# CheetahBooster.net
KiCad netlist of a schematic drawn in EAGLE
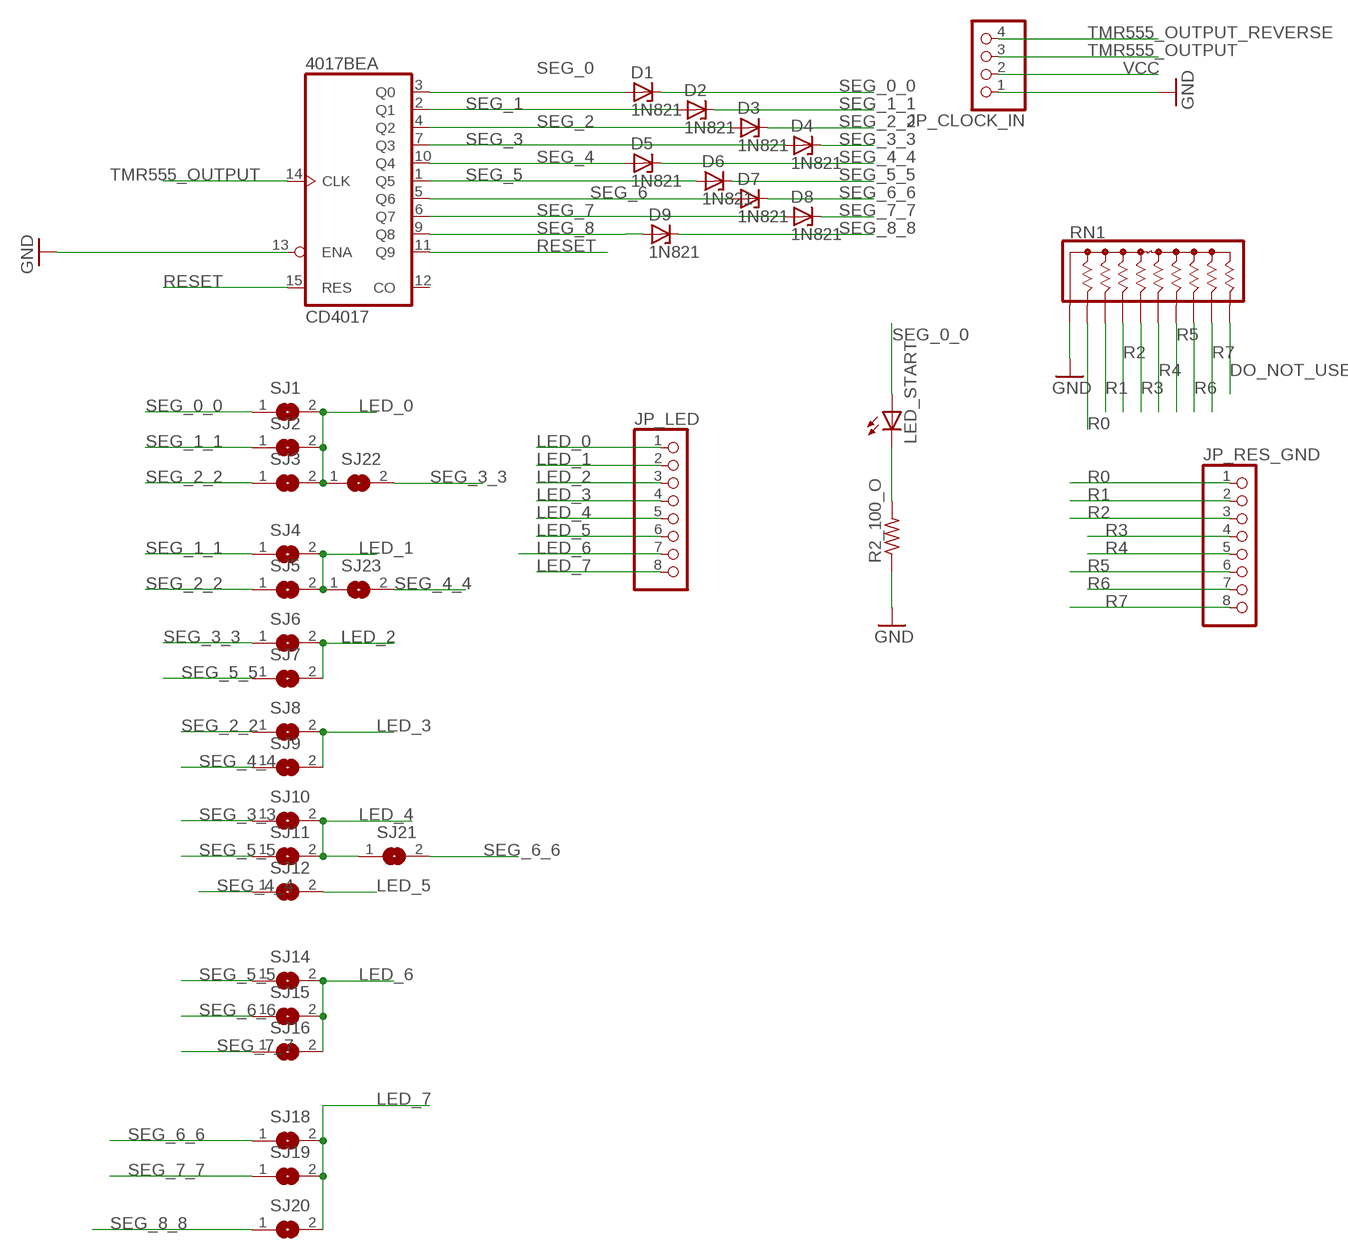
[diagram p0: schematic, sheet 1]

(export (version "E")
  (design (tool "Eeschema 10.0.6"))
  (components
    (comp (ref "4017BE")
      (value "CD4017")
      (footprint "eagle-import:DIL16")
      (libsource (lib "eagle-import") (part "CD4017"))
    )
    (comp (ref "D1")
      (value "1N821")
      (footprint "eagle-import:DO35Z10")
      (libsource (lib "eagle-import") (part "1N821"))
    )
    (comp (ref "D2")
      (value "1N821")
      (footprint "eagle-import:DO35Z10")
      (libsource (lib "eagle-import") (part "1N821"))
    )
    (comp (ref "D3")
      (value "1N821")
      (footprint "eagle-import:DO35Z10")
      (libsource (lib "eagle-import") (part "1N821"))
    )
    (comp (ref "D4")
      (value "1N821")
      (footprint "eagle-import:DO35Z10")
      (libsource (lib "eagle-import") (part "1N821"))
    )
    (comp (ref "D5")
      (value "1N821")
      (footprint "eagle-import:DO35Z10")
      (libsource (lib "eagle-import") (part "1N821"))
    )
    (comp (ref "D6")
      (value "1N821")
      (footprint "eagle-import:DO35Z10")
      (libsource (lib "eagle-import") (part "1N821"))
    )
    (comp (ref "D7")
      (value "1N821")
      (footprint "eagle-import:DO35Z10")
      (libsource (lib "eagle-import") (part "1N821"))
    )
    (comp (ref "D8")
      (value "1N821")
      (footprint "eagle-import:DO35Z10")
      (libsource (lib "eagle-import") (part "1N821"))
    )
    (comp (ref "D9")
      (value "1N821")
      (footprint "eagle-import:DO35Z10")
      (libsource (lib "eagle-import") (part "1N821"))
    )
    (comp (ref "JP_CLOCK_IN")
      (value "PINHD-1X4")
      (footprint "eagle-import:1X04")
      (libsource (lib "eagle-import") (part "PINHD-1X4"))
    )
    (comp (ref "JP_LED")
      (value "PINHD-1X8")
      (footprint "eagle-import:1X08")
      (libsource (lib "eagle-import") (part "PINHD-1X8"))
    )
    (comp (ref "JP_RES_GND")
      (value "PINHD-1X8")
      (footprint "eagle-import:1X08")
      (libsource (lib "eagle-import") (part "PINHD-1X8"))
    )
    (comp (ref "LED_START")
      (value "LEDSMT1206")
      (footprint "eagle-import:1206")
      (libsource (lib "eagle-import") (part "LEDSMT1206"))
    )
    (comp (ref "R2_100_O")
      (value "R-US_R1206")
      (footprint "eagle-import:R1206")
      (libsource (lib "eagle-import") (part "R-US_R1206"))
    )
    (comp (ref "RN1")
      (value "4610X")
      (footprint "eagle-import:SIP10")
      (libsource (lib "eagle-import") (part "4610X"))
    )
    (comp (ref "SJ1")
      (value "SOLDERJUMPER")
      (footprint "eagle-import:SOLDERJUMPER_ARROW_NOPASTE")
      (libsource (lib "eagle-import") (part "SOLDERJUMPER"))
    )
    (comp (ref "SJ2")
      (value "SOLDERJUMPER")
      (footprint "eagle-import:SOLDERJUMPER_ARROW_NOPASTE")
      (libsource (lib "eagle-import") (part "SOLDERJUMPER"))
    )
    (comp (ref "SJ3")
      (value "SOLDERJUMPER")
      (footprint "eagle-import:SOLDERJUMPER_ARROW_NOPASTE")
      (libsource (lib "eagle-import") (part "SOLDERJUMPER"))
    )
    (comp (ref "SJ4")
      (value "SOLDERJUMPER")
      (footprint "eagle-import:SOLDERJUMPER_ARROW_NOPASTE")
      (libsource (lib "eagle-import") (part "SOLDERJUMPER"))
    )
    (comp (ref "SJ5")
      (value "SOLDERJUMPER")
      (footprint "eagle-import:SOLDERJUMPER_ARROW_NOPASTE")
      (libsource (lib "eagle-import") (part "SOLDERJUMPER"))
    )
    (comp (ref "SJ6")
      (value "SOLDERJUMPER")
      (footprint "eagle-import:SOLDERJUMPER_ARROW_NOPASTE")
      (libsource (lib "eagle-import") (part "SOLDERJUMPER"))
    )
    (comp (ref "SJ7")
      (value "SOLDERJUMPER")
      (footprint "eagle-import:SOLDERJUMPER_ARROW_NOPASTE")
      (libsource (lib "eagle-import") (part "SOLDERJUMPER"))
    )
    (comp (ref "SJ8")
      (value "SOLDERJUMPER")
      (footprint "eagle-import:SOLDERJUMPER_ARROW_NOPASTE")
      (libsource (lib "eagle-import") (part "SOLDERJUMPER"))
    )
    (comp (ref "SJ9")
      (value "SOLDERJUMPER")
      (footprint "eagle-import:SOLDERJUMPER_ARROW_NOPASTE")
      (libsource (lib "eagle-import") (part "SOLDERJUMPER"))
    )
    (comp (ref "SJ10")
      (value "SOLDERJUMPER")
      (footprint "eagle-import:SOLDERJUMPER_ARROW_NOPASTE")
      (libsource (lib "eagle-import") (part "SOLDERJUMPER"))
    )
    (comp (ref "SJ11")
      (value "SOLDERJUMPER")
      (footprint "eagle-import:SOLDERJUMPER_ARROW_NOPASTE")
      (libsource (lib "eagle-import") (part "SOLDERJUMPER"))
    )
    (comp (ref "SJ12")
      (value "SOLDERJUMPER")
      (footprint "eagle-import:SOLDERJUMPER_ARROW_NOPASTE")
      (libsource (lib "eagle-import") (part "SOLDERJUMPER"))
    )
    (comp (ref "SJ14")
      (value "SOLDERJUMPER")
      (footprint "eagle-import:SOLDERJUMPER_ARROW_NOPASTE")
      (libsource (lib "eagle-import") (part "SOLDERJUMPER"))
    )
    (comp (ref "SJ15")
      (value "SOLDERJUMPER")
      (footprint "eagle-import:SOLDERJUMPER_ARROW_NOPASTE")
      (libsource (lib "eagle-import") (part "SOLDERJUMPER"))
    )
    (comp (ref "SJ16")
      (value "SOLDERJUMPER")
      (footprint "eagle-import:SOLDERJUMPER_ARROW_NOPASTE")
      (libsource (lib "eagle-import") (part "SOLDERJUMPER"))
    )
    (comp (ref "SJ18")
      (value "SOLDERJUMPER")
      (footprint "eagle-import:SOLDERJUMPER_ARROW_NOPASTE")
      (libsource (lib "eagle-import") (part "SOLDERJUMPER"))
    )
    (comp (ref "SJ19")
      (value "SOLDERJUMPER")
      (footprint "eagle-import:SOLDERJUMPER_ARROW_NOPASTE")
      (libsource (lib "eagle-import") (part "SOLDERJUMPER"))
    )
    (comp (ref "SJ20")
      (value "SOLDERJUMPER")
      (footprint "eagle-import:SOLDERJUMPER_ARROW_NOPASTE")
      (libsource (lib "eagle-import") (part "SOLDERJUMPER"))
    )
    (comp (ref "SJ21")
      (value "SOLDERJUMPER")
      (footprint "eagle-import:SOLDERJUMPER_ARROW_NOPASTE")
      (libsource (lib "eagle-import") (part "SOLDERJUMPER"))
    )
    (comp (ref "SJ22")
      (value "SOLDERJUMPER")
      (footprint "eagle-import:SOLDERJUMPER_ARROW_NOPASTE")
      (libsource (lib "eagle-import") (part "SOLDERJUMPER"))
    )
    (comp (ref "SJ23")
      (value "SOLDERJUMPER")
      (footprint "eagle-import:SOLDERJUMPER_ARROW_NOPASTE")
      (libsource (lib "eagle-import") (part "SOLDERJUMPER"))
    )
  )
  (nets
    (net (code "1") (name "/DO_NOT_USE") (class "Default")
      (node (ref "RN1") (pin "10") (pinfunction "10_10") (pintype "passive"))
    )
    (net (code "2") (name "/LED_0") (class "Default")
      (node (ref "JP_LED") (pin "1") (pinfunction "1_1") (pintype "passive"))
      (node (ref "SJ1") (pin "2") (pinfunction "2_2") (pintype "passive"))
      (node (ref "SJ2") (pin "2") (pinfunction "2_2") (pintype "passive"))
      (node (ref "SJ22") (pin "1") (pinfunction "1_1") (pintype "passive"))
      (node (ref "SJ3") (pin "2") (pinfunction "2_2") (pintype "passive"))
    )
    (net (code "3") (name "/LED_1") (class "Default")
      (node (ref "JP_LED") (pin "2") (pinfunction "2_2") (pintype "passive"))
      (node (ref "SJ23") (pin "1") (pinfunction "1_1") (pintype "passive"))
      (node (ref "SJ4") (pin "2") (pinfunction "2_2") (pintype "passive"))
      (node (ref "SJ5") (pin "2") (pinfunction "2_2") (pintype "passive"))
    )
    (net (code "4") (name "/LED_2") (class "Default")
      (node (ref "JP_LED") (pin "3") (pinfunction "3_3") (pintype "passive"))
      (node (ref "SJ6") (pin "2") (pinfunction "2_2") (pintype "passive"))
      (node (ref "SJ7") (pin "2") (pinfunction "2_2") (pintype "passive"))
    )
    (net (code "5") (name "/LED_3") (class "Default")
      (node (ref "JP_LED") (pin "4") (pinfunction "4_4") (pintype "passive"))
      (node (ref "SJ8") (pin "2") (pinfunction "2_2") (pintype "passive"))
      (node (ref "SJ9") (pin "2") (pinfunction "2_2") (pintype "passive"))
    )
    (net (code "6") (name "/LED_4") (class "Default")
      (node (ref "JP_LED") (pin "5") (pinfunction "5_5") (pintype "passive"))
      (node (ref "SJ10") (pin "2") (pinfunction "2_2") (pintype "passive"))
      (node (ref "SJ11") (pin "2") (pinfunction "2_2") (pintype "passive"))
      (node (ref "SJ21") (pin "1") (pinfunction "1_1") (pintype "passive"))
    )
    (net (code "7") (name "/LED_5") (class "Default")
      (node (ref "JP_LED") (pin "6") (pinfunction "6_6") (pintype "passive"))
      (node (ref "SJ12") (pin "2") (pinfunction "2_2") (pintype "passive"))
    )
    (net (code "8") (name "/LED_6") (class "Default")
      (node (ref "JP_LED") (pin "7") (pinfunction "7_7") (pintype "passive"))
      (node (ref "SJ14") (pin "2") (pinfunction "2_2") (pintype "passive"))
      (node (ref "SJ15") (pin "2") (pinfunction "2_2") (pintype "passive"))
      (node (ref "SJ16") (pin "2") (pinfunction "2_2") (pintype "passive"))
    )
    (net (code "9") (name "/LED_7") (class "Default")
      (node (ref "JP_LED") (pin "8") (pinfunction "8_8") (pintype "passive"))
      (node (ref "SJ18") (pin "2") (pinfunction "2_2") (pintype "passive"))
      (node (ref "SJ19") (pin "2") (pinfunction "2_2") (pintype "passive"))
      (node (ref "SJ20") (pin "2") (pinfunction "2_2") (pintype "passive"))
    )
    (net (code "10") (name "/R0") (class "Default")
      (node (ref "JP_RES_GND") (pin "1") (pinfunction "1_1") (pintype "passive"))
      (node (ref "RN1") (pin "2") (pinfunction "2_2") (pintype "passive"))
    )
    (net (code "11") (name "/R1") (class "Default")
      (node (ref "JP_RES_GND") (pin "2") (pinfunction "2_2") (pintype "passive"))
      (node (ref "RN1") (pin "3") (pinfunction "3_3") (pintype "passive"))
    )
    (net (code "12") (name "/R2") (class "Default")
      (node (ref "JP_RES_GND") (pin "3") (pinfunction "3_3") (pintype "passive"))
      (node (ref "RN1") (pin "4") (pinfunction "4_4") (pintype "passive"))
    )
    (net (code "13") (name "/R3") (class "Default")
      (node (ref "JP_RES_GND") (pin "4") (pinfunction "4_4") (pintype "passive"))
      (node (ref "RN1") (pin "5") (pinfunction "5_5") (pintype "passive"))
    )
    (net (code "14") (name "/R4") (class "Default")
      (node (ref "JP_RES_GND") (pin "5") (pinfunction "5_5") (pintype "passive"))
      (node (ref "RN1") (pin "6") (pinfunction "6_6") (pintype "passive"))
    )
    (net (code "15") (name "/R5") (class "Default")
      (node (ref "JP_RES_GND") (pin "6") (pinfunction "6_6") (pintype "passive"))
      (node (ref "RN1") (pin "7") (pinfunction "7_7") (pintype "passive"))
    )
    (net (code "16") (name "/R6") (class "Default")
      (node (ref "JP_RES_GND") (pin "7") (pinfunction "7_7") (pintype "passive"))
      (node (ref "RN1") (pin "8") (pinfunction "8_8") (pintype "passive"))
    )
    (net (code "17") (name "/R7") (class "Default")
      (node (ref "JP_RES_GND") (pin "8") (pinfunction "8_8") (pintype "passive"))
      (node (ref "RN1") (pin "9") (pinfunction "9_9") (pintype "passive"))
    )
    (net (code "18") (name "/RESET") (class "Default")
      (node (ref "4017BE") (pin "11") (pinfunction "Q9_11") (pintype "output"))
      (node (ref "4017BE") (pin "15") (pinfunction "RES_15") (pintype "input"))
    )
    (net (code "19") (name "/SEG_0") (class "Default")
      (node (ref "4017BE") (pin "3") (pinfunction "Q0_3") (pintype "output"))
      (node (ref "D1") (pin "A") (pinfunction "A_A") (pintype "passive"))
    )
    (net (code "20") (name "/SEG_0_0") (class "Default")
      (node (ref "D1") (pin "C") (pinfunction "C_C") (pintype "passive"))
      (node (ref "LED_START") (pin "A") (pinfunction "A_A") (pintype "passive"))
      (node (ref "SJ1") (pin "1") (pinfunction "1_1") (pintype "passive"))
    )
    (net (code "21") (name "/SEG_1") (class "Default")
      (node (ref "4017BE") (pin "2") (pinfunction "Q1_2") (pintype "output"))
      (node (ref "D2") (pin "A") (pinfunction "A_A") (pintype "passive"))
    )
    (net (code "22") (name "/SEG_1_1") (class "Default")
      (node (ref "D2") (pin "C") (pinfunction "C_C") (pintype "passive"))
      (node (ref "SJ2") (pin "1") (pinfunction "1_1") (pintype "passive"))
      (node (ref "SJ4") (pin "1") (pinfunction "1_1") (pintype "passive"))
    )
    (net (code "23") (name "/SEG_2") (class "Default")
      (node (ref "4017BE") (pin "4") (pinfunction "Q2_4") (pintype "output"))
      (node (ref "D3") (pin "A") (pinfunction "A_A") (pintype "passive"))
    )
    (net (code "24") (name "/SEG_2_2") (class "Default")
      (node (ref "D3") (pin "C") (pinfunction "C_C") (pintype "passive"))
      (node (ref "SJ3") (pin "1") (pinfunction "1_1") (pintype "passive"))
      (node (ref "SJ5") (pin "1") (pinfunction "1_1") (pintype "passive"))
      (node (ref "SJ8") (pin "1") (pinfunction "1_1") (pintype "passive"))
    )
    (net (code "25") (name "/SEG_3") (class "Default")
      (node (ref "4017BE") (pin "7") (pinfunction "Q3_7") (pintype "output"))
      (node (ref "D4") (pin "A") (pinfunction "A_A") (pintype "passive"))
    )
    (net (code "26") (name "/SEG_3_3") (class "Default")
      (node (ref "D4") (pin "C") (pinfunction "C_C") (pintype "passive"))
      (node (ref "SJ10") (pin "1") (pinfunction "1_1") (pintype "passive"))
      (node (ref "SJ22") (pin "2") (pinfunction "2_2") (pintype "passive"))
      (node (ref "SJ6") (pin "1") (pinfunction "1_1") (pintype "passive"))
    )
    (net (code "27") (name "/SEG_4") (class "Default")
      (node (ref "4017BE") (pin "10") (pinfunction "Q4_10") (pintype "output"))
      (node (ref "D5") (pin "A") (pinfunction "A_A") (pintype "passive"))
    )
    (net (code "28") (name "/SEG_4_4") (class "Default")
      (node (ref "D5") (pin "C") (pinfunction "C_C") (pintype "passive"))
      (node (ref "SJ12") (pin "1") (pinfunction "1_1") (pintype "passive"))
      (node (ref "SJ23") (pin "2") (pinfunction "2_2") (pintype "passive"))
      (node (ref "SJ9") (pin "1") (pinfunction "1_1") (pintype "passive"))
    )
    (net (code "29") (name "/SEG_5") (class "Default")
      (node (ref "4017BE") (pin "1") (pinfunction "Q5_1") (pintype "output"))
      (node (ref "D6") (pin "A") (pinfunction "A_A") (pintype "passive"))
    )
    (net (code "30") (name "/SEG_5_5") (class "Default")
      (node (ref "D6") (pin "C") (pinfunction "C_C") (pintype "passive"))
      (node (ref "SJ11") (pin "1") (pinfunction "1_1") (pintype "passive"))
      (node (ref "SJ14") (pin "1") (pinfunction "1_1") (pintype "passive"))
      (node (ref "SJ7") (pin "1") (pinfunction "1_1") (pintype "passive"))
    )
    (net (code "31") (name "/SEG_6") (class "Default")
      (node (ref "4017BE") (pin "5") (pinfunction "Q6_5") (pintype "output"))
      (node (ref "D7") (pin "A") (pinfunction "A_A") (pintype "passive"))
    )
    (net (code "32") (name "/SEG_6_6") (class "Default")
      (node (ref "D7") (pin "C") (pinfunction "C_C") (pintype "passive"))
      (node (ref "SJ15") (pin "1") (pinfunction "1_1") (pintype "passive"))
      (node (ref "SJ18") (pin "1") (pinfunction "1_1") (pintype "passive"))
      (node (ref "SJ21") (pin "2") (pinfunction "2_2") (pintype "passive"))
    )
    (net (code "33") (name "/SEG_7") (class "Default")
      (node (ref "4017BE") (pin "6") (pinfunction "Q7_6") (pintype "output"))
      (node (ref "D8") (pin "A") (pinfunction "A_A") (pintype "passive"))
    )
    (net (code "34") (name "/SEG_7_7") (class "Default")
      (node (ref "D8") (pin "C") (pinfunction "C_C") (pintype "passive"))
      (node (ref "SJ16") (pin "1") (pinfunction "1_1") (pintype "passive"))
      (node (ref "SJ19") (pin "1") (pinfunction "1_1") (pintype "passive"))
    )
    (net (code "35") (name "/SEG_8") (class "Default")
      (node (ref "4017BE") (pin "9") (pinfunction "Q8_9") (pintype "output"))
      (node (ref "D9") (pin "A") (pinfunction "A_A") (pintype "passive"))
    )
    (net (code "36") (name "/SEG_8_8") (class "Default")
      (node (ref "D9") (pin "C") (pinfunction "C_C") (pintype "passive"))
      (node (ref "SJ20") (pin "1") (pinfunction "1_1") (pintype "passive"))
    )
    (net (code "37") (name "/TMR555_OUTPUT") (class "Default")
      (node (ref "4017BE") (pin "14") (pinfunction "CLK_14") (pintype "input"))
      (node (ref "JP_CLOCK_IN") (pin "3") (pinfunction "3_3") (pintype "passive"))
    )
    (net (code "38") (name "/TMR555_OUTPUT_REVERSE") (class "Default")
      (node (ref "JP_CLOCK_IN") (pin "4") (pinfunction "4_4") (pintype "passive"))
    )
    (net (code "39") (name "/VCC") (class "Default")
      (node (ref "JP_CLOCK_IN") (pin "2") (pinfunction "2_2") (pintype "passive"))
    )
    (net (code "40") (name "GND") (class "Default")
      (node (ref "4017BE") (pin "13") (pinfunction "ENA_13") (pintype "input"))
      (node (ref "JP_CLOCK_IN") (pin "1") (pinfunction "1_1") (pintype "passive"))
      (node (ref "R2_100_O") (pin "1") (pinfunction "1_1") (pintype "passive"))
      (node (ref "RN1") (pin "1") (pinfunction "1_1") (pintype "passive"))
    )
    (net (code "41") (name "Net-(LED_START-PadC)") (class "Default")
      (node (ref "LED_START") (pin "C") (pinfunction "C_C") (pintype "passive"))
      (node (ref "R2_100_O") (pin "2") (pinfunction "2_2") (pintype "passive"))
    )
    (net (code "42") (name "unconnected-(4017BEA-CO-Pad12)") (class "Default")
      (node (ref "4017BE") (pin "12") (pinfunction "CO_12") (pintype "output"))
    )
  )
)
